# con-left-top.net
KiCad netlist of a schematic drawn in Altium Designer
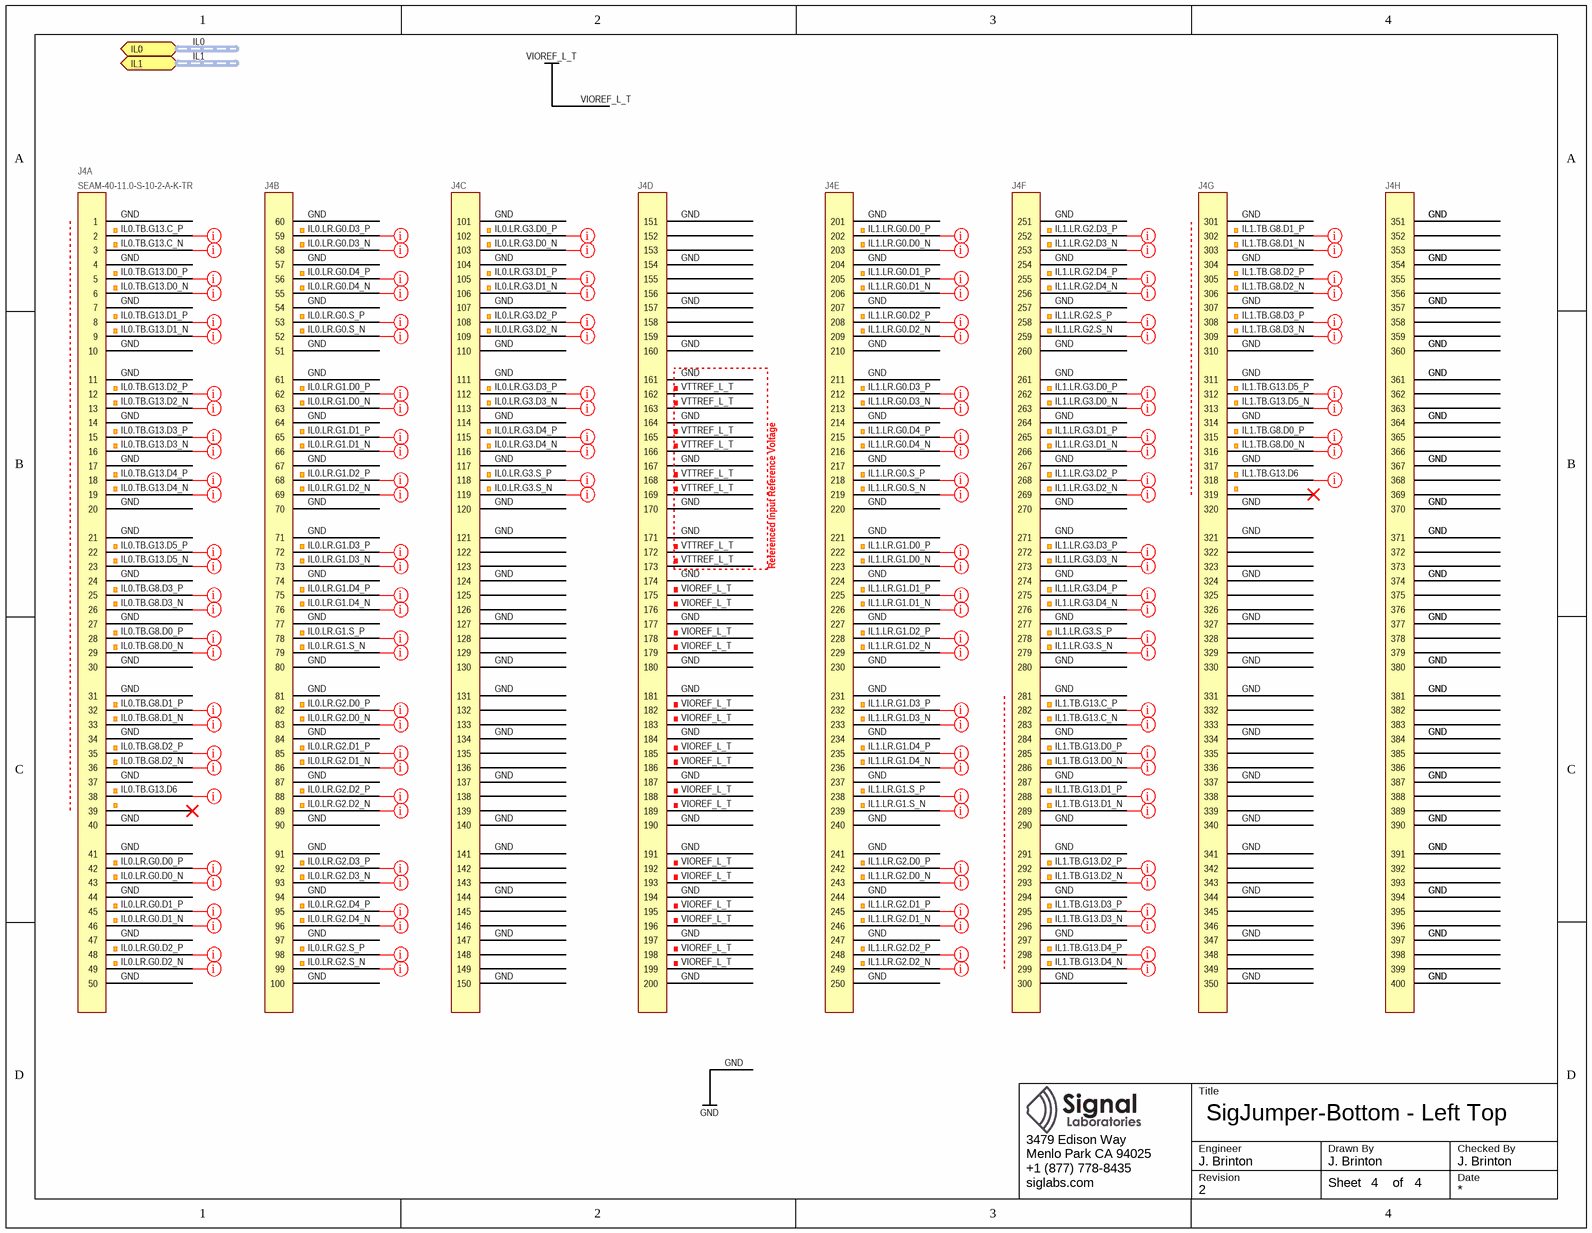
[diagram p0: con-left-top.SchDoc]

(export (version "E")
  (design (tool "Eeschema 10.0.6"))
  (components
    (comp (ref "J4")
      (value "SEAM-40-11.0-S-10-2-A-K-TR")
      (footprint "samtec:SEAM-40-11.0-S-10-2-A-K-TR")
      (description "Terminal Array Assembly, Surface Mount, 0.050\" Pitch, 400 Pins")
      (fields (field (name "MANUFACTURER") "Samtec"))
      (libsource (lib "samtec") (part "SEAM-40-11.0-S-10-2-A-K-TR"))
    )
  )
  (nets
    (net (code "3") (name "/IL0.LR.G0.D0_N") (class "Default")
      (node (ref "J4") (pin "43") (pinfunction "43_43") (pintype "passive"))
    )
    (net (code "4") (name "/IL0.LR.G0.D0_P") (class "Default")
      (node (ref "J4") (pin "42") (pinfunction "42_42") (pintype "passive"))
    )
    (net (code "5") (name "/IL0.LR.G0.D1_N") (class "Default")
      (node (ref "J4") (pin "46") (pinfunction "46_46") (pintype "passive"))
    )
    (net (code "6") (name "/IL0.LR.G0.D1_P") (class "Default")
      (node (ref "J4") (pin "45") (pinfunction "45_45") (pintype "passive"))
    )
    (net (code "7") (name "/IL0.LR.G0.D2_N") (class "Default")
      (node (ref "J4") (pin "49") (pinfunction "49_49") (pintype "passive"))
    )
    (net (code "8") (name "/IL0.LR.G0.D2_P") (class "Default")
      (node (ref "J4") (pin "48") (pinfunction "48_48") (pintype "passive"))
    )
    (net (code "9") (name "/IL0.LR.G0.D3_N") (class "Default")
      (node (ref "J4") (pin "58") (pinfunction "58_58") (pintype "passive"))
    )
    (net (code "10") (name "/IL0.LR.G0.D3_P") (class "Default")
      (node (ref "J4") (pin "59") (pinfunction "59_59") (pintype "passive"))
    )
    (net (code "11") (name "/IL0.LR.G0.D4_N") (class "Default")
      (node (ref "J4") (pin "55") (pinfunction "55_55") (pintype "passive"))
    )
    (net (code "12") (name "/IL0.LR.G0.D4_P") (class "Default")
      (node (ref "J4") (pin "56") (pinfunction "56_56") (pintype "passive"))
    )
    (net (code "13") (name "/IL0.LR.G0.S_N") (class "Default")
      (node (ref "J4") (pin "52") (pinfunction "52_52") (pintype "passive"))
    )
    (net (code "14") (name "/IL0.LR.G0.S_P") (class "Default")
      (node (ref "J4") (pin "53") (pinfunction "53_53") (pintype "passive"))
    )
    (net (code "15") (name "/IL0.LR.G1.D0_N") (class "Default")
      (node (ref "J4") (pin "63") (pinfunction "63_63") (pintype "passive"))
    )
    (net (code "16") (name "/IL0.LR.G1.D0_P") (class "Default")
      (node (ref "J4") (pin "62") (pinfunction "62_62") (pintype "passive"))
    )
    (net (code "17") (name "/IL0.LR.G1.D1_N") (class "Default")
      (node (ref "J4") (pin "66") (pinfunction "66_66") (pintype "passive"))
    )
    (net (code "18") (name "/IL0.LR.G1.D1_P") (class "Default")
      (node (ref "J4") (pin "65") (pinfunction "65_65") (pintype "passive"))
    )
    (net (code "19") (name "/IL0.LR.G1.D2_N") (class "Default")
      (node (ref "J4") (pin "69") (pinfunction "69_69") (pintype "passive"))
    )
    (net (code "20") (name "/IL0.LR.G1.D2_P") (class "Default")
      (node (ref "J4") (pin "68") (pinfunction "68_68") (pintype "passive"))
    )
    (net (code "21") (name "/IL0.LR.G1.D3_N") (class "Default")
      (node (ref "J4") (pin "73") (pinfunction "73_73") (pintype "passive"))
    )
    (net (code "22") (name "/IL0.LR.G1.D3_P") (class "Default")
      (node (ref "J4") (pin "72") (pinfunction "72_72") (pintype "passive"))
    )
    (net (code "23") (name "/IL0.LR.G1.D4_N") (class "Default")
      (node (ref "J4") (pin "76") (pinfunction "76_76") (pintype "passive"))
    )
    (net (code "24") (name "/IL0.LR.G1.D4_P") (class "Default")
      (node (ref "J4") (pin "75") (pinfunction "75_75") (pintype "passive"))
    )
    (net (code "25") (name "/IL0.LR.G1.S_N") (class "Default")
      (node (ref "J4") (pin "79") (pinfunction "79_79") (pintype "passive"))
    )
    (net (code "26") (name "/IL0.LR.G1.S_P") (class "Default")
      (node (ref "J4") (pin "78") (pinfunction "78_78") (pintype "passive"))
    )
    (net (code "27") (name "/IL0.LR.G2.D0_N") (class "Default")
      (node (ref "J4") (pin "83") (pinfunction "83_83") (pintype "passive"))
    )
    (net (code "28") (name "/IL0.LR.G2.D0_P") (class "Default")
      (node (ref "J4") (pin "82") (pinfunction "82_82") (pintype "passive"))
    )
    (net (code "29") (name "/IL0.LR.G2.D1_N") (class "Default")
      (node (ref "J4") (pin "86") (pinfunction "86_86") (pintype "passive"))
    )
    (net (code "30") (name "/IL0.LR.G2.D1_P") (class "Default")
      (node (ref "J4") (pin "85") (pinfunction "85_85") (pintype "passive"))
    )
    (net (code "31") (name "/IL0.LR.G2.D2_N") (class "Default")
      (node (ref "J4") (pin "89") (pinfunction "89_89") (pintype "passive"))
    )
    (net (code "32") (name "/IL0.LR.G2.D2_P") (class "Default")
      (node (ref "J4") (pin "88") (pinfunction "88_88") (pintype "passive"))
    )
    (net (code "33") (name "/IL0.LR.G2.D3_N") (class "Default")
      (node (ref "J4") (pin "93") (pinfunction "93_93") (pintype "passive"))
    )
    (net (code "34") (name "/IL0.LR.G2.D3_P") (class "Default")
      (node (ref "J4") (pin "92") (pinfunction "92_92") (pintype "passive"))
    )
    (net (code "35") (name "/IL0.LR.G2.D4_N") (class "Default")
      (node (ref "J4") (pin "96") (pinfunction "96_96") (pintype "passive"))
    )
    (net (code "36") (name "/IL0.LR.G2.D4_P") (class "Default")
      (node (ref "J4") (pin "95") (pinfunction "95_95") (pintype "passive"))
    )
    (net (code "37") (name "/IL0.LR.G2.S_N") (class "Default")
      (node (ref "J4") (pin "99") (pinfunction "99_99") (pintype "passive"))
    )
    (net (code "38") (name "/IL0.LR.G2.S_P") (class "Default")
      (node (ref "J4") (pin "98") (pinfunction "98_98") (pintype "passive"))
    )
    (net (code "39") (name "/IL0.LR.G3.D0_N") (class "Default")
      (node (ref "J4") (pin "103") (pinfunction "103_103") (pintype "passive"))
    )
    (net (code "40") (name "/IL0.LR.G3.D0_P") (class "Default")
      (node (ref "J4") (pin "102") (pinfunction "102_102") (pintype "passive"))
    )
    (net (code "41") (name "/IL0.LR.G3.D1_N") (class "Default")
      (node (ref "J4") (pin "106") (pinfunction "106_106") (pintype "passive"))
    )
    (net (code "42") (name "/IL0.LR.G3.D1_P") (class "Default")
      (node (ref "J4") (pin "105") (pinfunction "105_105") (pintype "passive"))
    )
    (net (code "43") (name "/IL0.LR.G3.D2_N") (class "Default")
      (node (ref "J4") (pin "109") (pinfunction "109_109") (pintype "passive"))
    )
    (net (code "44") (name "/IL0.LR.G3.D2_P") (class "Default")
      (node (ref "J4") (pin "108") (pinfunction "108_108") (pintype "passive"))
    )
    (net (code "45") (name "/IL0.LR.G3.D3_N") (class "Default")
      (node (ref "J4") (pin "113") (pinfunction "113_113") (pintype "passive"))
    )
    (net (code "46") (name "/IL0.LR.G3.D3_P") (class "Default")
      (node (ref "J4") (pin "112") (pinfunction "112_112") (pintype "passive"))
    )
    (net (code "47") (name "/IL0.LR.G3.D4_N") (class "Default")
      (node (ref "J4") (pin "116") (pinfunction "116_116") (pintype "passive"))
    )
    (net (code "48") (name "/IL0.LR.G3.D4_P") (class "Default")
      (node (ref "J4") (pin "115") (pinfunction "115_115") (pintype "passive"))
    )
    (net (code "49") (name "/IL0.LR.G3.S_N") (class "Default")
      (node (ref "J4") (pin "119") (pinfunction "119_119") (pintype "passive"))
    )
    (net (code "50") (name "/IL0.LR.G3.S_P") (class "Default")
      (node (ref "J4") (pin "118") (pinfunction "118_118") (pintype "passive"))
    )
    (net (code "51") (name "/IL0.TB.G8.D0_N") (class "Default")
      (node (ref "J4") (pin "29") (pinfunction "29_29") (pintype "passive"))
    )
    (net (code "52") (name "/IL0.TB.G8.D0_P") (class "Default")
      (node (ref "J4") (pin "28") (pinfunction "28_28") (pintype "passive"))
    )
    (net (code "53") (name "/IL0.TB.G8.D1_N") (class "Default")
      (node (ref "J4") (pin "33") (pinfunction "33_33") (pintype "passive"))
    )
    (net (code "54") (name "/IL0.TB.G8.D1_P") (class "Default")
      (node (ref "J4") (pin "32") (pinfunction "32_32") (pintype "passive"))
    )
    (net (code "55") (name "/IL0.TB.G8.D2_N") (class "Default")
      (node (ref "J4") (pin "36") (pinfunction "36_36") (pintype "passive"))
    )
    (net (code "56") (name "/IL0.TB.G8.D2_P") (class "Default")
      (node (ref "J4") (pin "35") (pinfunction "35_35") (pintype "passive"))
    )
    (net (code "57") (name "/IL0.TB.G8.D3_N") (class "Default")
      (node (ref "J4") (pin "26") (pinfunction "26_26") (pintype "passive"))
    )
    (net (code "58") (name "/IL0.TB.G8.D3_P") (class "Default")
      (node (ref "J4") (pin "25") (pinfunction "25_25") (pintype "passive"))
    )
    (net (code "59") (name "/IL0.TB.G13.C_N") (class "Default")
      (node (ref "J4") (pin "3") (pinfunction "3_3") (pintype "passive"))
    )
    (net (code "60") (name "/IL0.TB.G13.C_P") (class "Default")
      (node (ref "J4") (pin "2") (pinfunction "2_2") (pintype "passive"))
    )
    (net (code "61") (name "/IL0.TB.G13.D0_N") (class "Default")
      (node (ref "J4") (pin "6") (pinfunction "6_6") (pintype "passive"))
    )
    (net (code "62") (name "/IL0.TB.G13.D0_P") (class "Default")
      (node (ref "J4") (pin "5") (pinfunction "5_5") (pintype "passive"))
    )
    (net (code "63") (name "/IL0.TB.G13.D1_N") (class "Default")
      (node (ref "J4") (pin "9") (pinfunction "9_9") (pintype "passive"))
    )
    (net (code "64") (name "/IL0.TB.G13.D1_P") (class "Default")
      (node (ref "J4") (pin "8") (pinfunction "8_8") (pintype "passive"))
    )
    (net (code "65") (name "/IL0.TB.G13.D2_N") (class "Default")
      (node (ref "J4") (pin "13") (pinfunction "13_13") (pintype "passive"))
    )
    (net (code "66") (name "/IL0.TB.G13.D2_P") (class "Default")
      (node (ref "J4") (pin "12") (pinfunction "12_12") (pintype "passive"))
    )
    (net (code "67") (name "/IL0.TB.G13.D3_N") (class "Default")
      (node (ref "J4") (pin "16") (pinfunction "16_16") (pintype "passive"))
    )
    (net (code "68") (name "/IL0.TB.G13.D3_P") (class "Default")
      (node (ref "J4") (pin "15") (pinfunction "15_15") (pintype "passive"))
    )
    (net (code "69") (name "/IL0.TB.G13.D4_N") (class "Default")
      (node (ref "J4") (pin "19") (pinfunction "19_19") (pintype "passive"))
    )
    (net (code "70") (name "/IL0.TB.G13.D4_P") (class "Default")
      (node (ref "J4") (pin "18") (pinfunction "18_18") (pintype "passive"))
    )
    (net (code "71") (name "/IL0.TB.G13.D5_N") (class "Default")
      (node (ref "J4") (pin "23") (pinfunction "23_23") (pintype "passive"))
    )
    (net (code "72") (name "/IL0.TB.G13.D5_P") (class "Default")
      (node (ref "J4") (pin "22") (pinfunction "22_22") (pintype "passive"))
    )
    (net (code "73") (name "/IL0.TB.G13.D6") (class "Default")
      (node (ref "J4") (pin "38") (pinfunction "38_38") (pintype "passive"))
    )
    (net (code "74") (name "/IL1.LR.G0.D0_N") (class "Default")
      (node (ref "J4") (pin "203") (pinfunction "203_203") (pintype "passive"))
    )
    (net (code "75") (name "/IL1.LR.G0.D0_P") (class "Default")
      (node (ref "J4") (pin "202") (pinfunction "202_202") (pintype "passive"))
    )
    (net (code "76") (name "/IL1.LR.G0.D1_N") (class "Default")
      (node (ref "J4") (pin "206") (pinfunction "206_206") (pintype "passive"))
    )
    (net (code "77") (name "/IL1.LR.G0.D1_P") (class "Default")
      (node (ref "J4") (pin "205") (pinfunction "205_205") (pintype "passive"))
    )
    (net (code "78") (name "/IL1.LR.G0.D2_N") (class "Default")
      (node (ref "J4") (pin "209") (pinfunction "209_209") (pintype "passive"))
    )
    (net (code "79") (name "/IL1.LR.G0.D2_P") (class "Default")
      (node (ref "J4") (pin "208") (pinfunction "208_208") (pintype "passive"))
    )
    (net (code "80") (name "/IL1.LR.G0.D3_N") (class "Default")
      (node (ref "J4") (pin "213") (pinfunction "213_213") (pintype "passive"))
    )
    (net (code "81") (name "/IL1.LR.G0.D3_P") (class "Default")
      (node (ref "J4") (pin "212") (pinfunction "212_212") (pintype "passive"))
    )
    (net (code "82") (name "/IL1.LR.G0.D4_N") (class "Default")
      (node (ref "J4") (pin "216") (pinfunction "216_216") (pintype "passive"))
    )
    (net (code "83") (name "/IL1.LR.G0.D4_P") (class "Default")
      (node (ref "J4") (pin "215") (pinfunction "215_215") (pintype "passive"))
    )
    (net (code "84") (name "/IL1.LR.G0.S_N") (class "Default")
      (node (ref "J4") (pin "219") (pinfunction "219_219") (pintype "passive"))
    )
    (net (code "85") (name "/IL1.LR.G0.S_P") (class "Default")
      (node (ref "J4") (pin "218") (pinfunction "218_218") (pintype "passive"))
    )
    (net (code "86") (name "/IL1.LR.G1.D0_N") (class "Default")
      (node (ref "J4") (pin "223") (pinfunction "223_223") (pintype "passive"))
    )
    (net (code "87") (name "/IL1.LR.G1.D0_P") (class "Default")
      (node (ref "J4") (pin "222") (pinfunction "222_222") (pintype "passive"))
    )
    (net (code "88") (name "/IL1.LR.G1.D1_N") (class "Default")
      (node (ref "J4") (pin "226") (pinfunction "226_226") (pintype "passive"))
    )
    (net (code "89") (name "/IL1.LR.G1.D1_P") (class "Default")
      (node (ref "J4") (pin "225") (pinfunction "225_225") (pintype "passive"))
    )
    (net (code "90") (name "/IL1.LR.G1.D2_N") (class "Default")
      (node (ref "J4") (pin "229") (pinfunction "229_229") (pintype "passive"))
    )
    (net (code "91") (name "/IL1.LR.G1.D2_P") (class "Default")
      (node (ref "J4") (pin "228") (pinfunction "228_228") (pintype "passive"))
    )
    (net (code "92") (name "/IL1.LR.G1.D3_N") (class "Default")
      (node (ref "J4") (pin "233") (pinfunction "233_233") (pintype "passive"))
    )
    (net (code "93") (name "/IL1.LR.G1.D3_P") (class "Default")
      (node (ref "J4") (pin "232") (pinfunction "232_232") (pintype "passive"))
    )
    (net (code "94") (name "/IL1.LR.G1.D4_N") (class "Default")
      (node (ref "J4") (pin "236") (pinfunction "236_236") (pintype "passive"))
    )
    (net (code "95") (name "/IL1.LR.G1.D4_P") (class "Default")
      (node (ref "J4") (pin "235") (pinfunction "235_235") (pintype "passive"))
    )
    (net (code "96") (name "/IL1.LR.G1.S_N") (class "Default")
      (node (ref "J4") (pin "239") (pinfunction "239_239") (pintype "passive"))
    )
    (net (code "97") (name "/IL1.LR.G1.S_P") (class "Default")
      (node (ref "J4") (pin "238") (pinfunction "238_238") (pintype "passive"))
    )
    (net (code "98") (name "/IL1.LR.G2.D0_N") (class "Default")
      (node (ref "J4") (pin "243") (pinfunction "243_243") (pintype "passive"))
    )
    (net (code "99") (name "/IL1.LR.G2.D0_P") (class "Default")
      (node (ref "J4") (pin "242") (pinfunction "242_242") (pintype "passive"))
    )
    (net (code "100") (name "/IL1.LR.G2.D1_N") (class "Default")
      (node (ref "J4") (pin "246") (pinfunction "246_246") (pintype "passive"))
    )
    (net (code "101") (name "/IL1.LR.G2.D1_P") (class "Default")
      (node (ref "J4") (pin "245") (pinfunction "245_245") (pintype "passive"))
    )
    (net (code "102") (name "/IL1.LR.G2.D2_N") (class "Default")
      (node (ref "J4") (pin "249") (pinfunction "249_249") (pintype "passive"))
    )
    (net (code "103") (name "/IL1.LR.G2.D2_P") (class "Default")
      (node (ref "J4") (pin "248") (pinfunction "248_248") (pintype "passive"))
    )
    (net (code "104") (name "/IL1.LR.G2.D3_N") (class "Default")
      (node (ref "J4") (pin "253") (pinfunction "253_253") (pintype "passive"))
    )
    (net (code "105") (name "/IL1.LR.G2.D3_P") (class "Default")
      (node (ref "J4") (pin "252") (pinfunction "252_252") (pintype "passive"))
    )
    (net (code "106") (name "/IL1.LR.G2.D4_N") (class "Default")
      (node (ref "J4") (pin "256") (pinfunction "256_256") (pintype "passive"))
    )
    (net (code "107") (name "/IL1.LR.G2.D4_P") (class "Default")
      (node (ref "J4") (pin "255") (pinfunction "255_255") (pintype "passive"))
    )
    (net (code "108") (name "/IL1.LR.G2.S_N") (class "Default")
      (node (ref "J4") (pin "259") (pinfunction "259_259") (pintype "passive"))
    )
    (net (code "109") (name "/IL1.LR.G2.S_P") (class "Default")
      (node (ref "J4") (pin "258") (pinfunction "258_258") (pintype "passive"))
    )
    (net (code "110") (name "/IL1.LR.G3.D0_N") (class "Default")
      (node (ref "J4") (pin "263") (pinfunction "263_263") (pintype "passive"))
    )
    (net (code "111") (name "/IL1.LR.G3.D0_P") (class "Default")
      (node (ref "J4") (pin "262") (pinfunction "262_262") (pintype "passive"))
    )
    (net (code "112") (name "/IL1.LR.G3.D1_N") (class "Default")
      (node (ref "J4") (pin "266") (pinfunction "266_266") (pintype "passive"))
    )
    (net (code "113") (name "/IL1.LR.G3.D1_P") (class "Default")
      (node (ref "J4") (pin "265") (pinfunction "265_265") (pintype "passive"))
    )
    (net (code "114") (name "/IL1.LR.G3.D2_N") (class "Default")
      (node (ref "J4") (pin "269") (pinfunction "269_269") (pintype "passive"))
    )
    (net (code "115") (name "/IL1.LR.G3.D2_P") (class "Default")
      (node (ref "J4") (pin "268") (pinfunction "268_268") (pintype "passive"))
    )
    (net (code "116") (name "/IL1.LR.G3.D3_N") (class "Default")
      (node (ref "J4") (pin "273") (pinfunction "273_273") (pintype "passive"))
    )
    (net (code "117") (name "/IL1.LR.G3.D3_P") (class "Default")
      (node (ref "J4") (pin "272") (pinfunction "272_272") (pintype "passive"))
    )
    (net (code "118") (name "/IL1.LR.G3.D4_N") (class "Default")
      (node (ref "J4") (pin "276") (pinfunction "276_276") (pintype "passive"))
    )
    (net (code "119") (name "/IL1.LR.G3.D4_P") (class "Default")
      (node (ref "J4") (pin "275") (pinfunction "275_275") (pintype "passive"))
    )
    (net (code "120") (name "/IL1.LR.G3.S_N") (class "Default")
      (node (ref "J4") (pin "279") (pinfunction "279_279") (pintype "passive"))
    )
    (net (code "121") (name "/IL1.LR.G3.S_P") (class "Default")
      (node (ref "J4") (pin "278") (pinfunction "278_278") (pintype "passive"))
    )
    (net (code "122") (name "/IL1.TB.G8.D0_N") (class "Default")
      (node (ref "J4") (pin "316") (pinfunction "316_316") (pintype "passive"))
    )
    (net (code "123") (name "/IL1.TB.G8.D0_P") (class "Default")
      (node (ref "J4") (pin "315") (pinfunction "315_315") (pintype "passive"))
    )
    (net (code "124") (name "/IL1.TB.G8.D1_N") (class "Default")
      (node (ref "J4") (pin "303") (pinfunction "303_303") (pintype "passive"))
    )
    (net (code "125") (name "/IL1.TB.G8.D1_P") (class "Default")
      (node (ref "J4") (pin "302") (pinfunction "302_302") (pintype "passive"))
    )
    (net (code "126") (name "/IL1.TB.G8.D2_N") (class "Default")
      (node (ref "J4") (pin "306") (pinfunction "306_306") (pintype "passive"))
    )
    (net (code "127") (name "/IL1.TB.G8.D2_P") (class "Default")
      (node (ref "J4") (pin "305") (pinfunction "305_305") (pintype "passive"))
    )
    (net (code "128") (name "/IL1.TB.G8.D3_N") (class "Default")
      (node (ref "J4") (pin "309") (pinfunction "309_309") (pintype "passive"))
    )
    (net (code "129") (name "/IL1.TB.G8.D3_P") (class "Default")
      (node (ref "J4") (pin "308") (pinfunction "308_308") (pintype "passive"))
    )
    (net (code "130") (name "/IL1.TB.G13.C_N") (class "Default")
      (node (ref "J4") (pin "283") (pinfunction "283_283") (pintype "passive"))
    )
    (net (code "131") (name "/IL1.TB.G13.C_P") (class "Default")
      (node (ref "J4") (pin "282") (pinfunction "282_282") (pintype "passive"))
    )
    (net (code "132") (name "/IL1.TB.G13.D0_N") (class "Default")
      (node (ref "J4") (pin "286") (pinfunction "286_286") (pintype "passive"))
    )
    (net (code "133") (name "/IL1.TB.G13.D0_P") (class "Default")
      (node (ref "J4") (pin "285") (pinfunction "285_285") (pintype "passive"))
    )
    (net (code "134") (name "/IL1.TB.G13.D1_N") (class "Default")
      (node (ref "J4") (pin "289") (pinfunction "289_289") (pintype "passive"))
    )
    (net (code "135") (name "/IL1.TB.G13.D1_P") (class "Default")
      (node (ref "J4") (pin "288") (pinfunction "288_288") (pintype "passive"))
    )
    (net (code "136") (name "/IL1.TB.G13.D2_N") (class "Default")
      (node (ref "J4") (pin "293") (pinfunction "293_293") (pintype "passive"))
    )
    (net (code "137") (name "/IL1.TB.G13.D2_P") (class "Default")
      (node (ref "J4") (pin "292") (pinfunction "292_292") (pintype "passive"))
    )
    (net (code "138") (name "/IL1.TB.G13.D3_N") (class "Default")
      (node (ref "J4") (pin "296") (pinfunction "296_296") (pintype "passive"))
    )
    (net (code "139") (name "/IL1.TB.G13.D3_P") (class "Default")
      (node (ref "J4") (pin "295") (pinfunction "295_295") (pintype "passive"))
    )
    (net (code "140") (name "/IL1.TB.G13.D4_N") (class "Default")
      (node (ref "J4") (pin "299") (pinfunction "299_299") (pintype "passive"))
    )
    (net (code "141") (name "/IL1.TB.G13.D4_P") (class "Default")
      (node (ref "J4") (pin "298") (pinfunction "298_298") (pintype "passive"))
    )
    (net (code "142") (name "/IL1.TB.G13.D5_N") (class "Default")
      (node (ref "J4") (pin "313") (pinfunction "313_313") (pintype "passive"))
    )
    (net (code "143") (name "/IL1.TB.G13.D5_P") (class "Default")
      (node (ref "J4") (pin "312") (pinfunction "312_312") (pintype "passive"))
    )
    (net (code "144") (name "/IL1.TB.G13.D6") (class "Default")
      (node (ref "J4") (pin "318") (pinfunction "318_318") (pintype "passive"))
    )
    (net (code "145") (name "/VTTREF_L_T") (class "Default")
      (node (ref "J4") (pin "162") (pinfunction "162_162") (pintype "passive"))
      (node (ref "J4") (pin "163") (pinfunction "163_163") (pintype "passive"))
      (node (ref "J4") (pin "165") (pinfunction "165_165") (pintype "passive"))
      (node (ref "J4") (pin "166") (pinfunction "166_166") (pintype "passive"))
      (node (ref "J4") (pin "168") (pinfunction "168_168") (pintype "passive"))
      (node (ref "J4") (pin "169") (pinfunction "169_169") (pintype "passive"))
      (node (ref "J4") (pin "172") (pinfunction "172_172") (pintype "passive"))
      (node (ref "J4") (pin "173") (pinfunction "173_173") (pintype "passive"))
    )
    (net (code "148") (name "GND") (class "Default")
      (node (ref "J4") (pin "1") (pinfunction "1_1") (pintype "passive"))
      (node (ref "J4") (pin "10") (pinfunction "10_10") (pintype "passive"))
      (node (ref "J4") (pin "100") (pinfunction "100_100") (pintype "passive"))
      (node (ref "J4") (pin "101") (pinfunction "101_101") (pintype "passive"))
      (node (ref "J4") (pin "104") (pinfunction "104_104") (pintype "passive"))
      (node (ref "J4") (pin "107") (pinfunction "107_107") (pintype "passive"))
      (node (ref "J4") (pin "11") (pinfunction "11_11") (pintype "passive"))
      (node (ref "J4") (pin "110") (pinfunction "110_110") (pintype "passive"))
      (node (ref "J4") (pin "111") (pinfunction "111_111") (pintype "passive"))
      (node (ref "J4") (pin "114") (pinfunction "114_114") (pintype "passive"))
      (node (ref "J4") (pin "117") (pinfunction "117_117") (pintype "passive"))
      (node (ref "J4") (pin "120") (pinfunction "120_120") (pintype "passive"))
      (node (ref "J4") (pin "121") (pinfunction "121_121") (pintype "passive"))
      (node (ref "J4") (pin "124") (pinfunction "124_124") (pintype "passive"))
      (node (ref "J4") (pin "127") (pinfunction "127_127") (pintype "passive"))
      (node (ref "J4") (pin "130") (pinfunction "130_130") (pintype "passive"))
      (node (ref "J4") (pin "131") (pinfunction "131_131") (pintype "passive"))
      (node (ref "J4") (pin "134") (pinfunction "134_134") (pintype "passive"))
      (node (ref "J4") (pin "137") (pinfunction "137_137") (pintype "passive"))
      (node (ref "J4") (pin "14") (pinfunction "14_14") (pintype "passive"))
      (node (ref "J4") (pin "140") (pinfunction "140_140") (pintype "passive"))
      (node (ref "J4") (pin "141") (pinfunction "141_141") (pintype "passive"))
      (node (ref "J4") (pin "144") (pinfunction "144_144") (pintype "passive"))
      (node (ref "J4") (pin "147") (pinfunction "147_147") (pintype "passive"))
      (node (ref "J4") (pin "150") (pinfunction "150_150") (pintype "passive"))
      (node (ref "J4") (pin "151") (pinfunction "151_151") (pintype "passive"))
      (node (ref "J4") (pin "154") (pinfunction "154_154") (pintype "passive"))
      (node (ref "J4") (pin "157") (pinfunction "157_157") (pintype "passive"))
      (node (ref "J4") (pin "160") (pinfunction "160_160") (pintype "passive"))
      (node (ref "J4") (pin "161") (pinfunction "161_161") (pintype "passive"))
      (node (ref "J4") (pin "164") (pinfunction "164_164") (pintype "passive"))
      (node (ref "J4") (pin "167") (pinfunction "167_167") (pintype "passive"))
      (node (ref "J4") (pin "17") (pinfunction "17_17") (pintype "passive"))
      (node (ref "J4") (pin "170") (pinfunction "170_170") (pintype "passive"))
      (node (ref "J4") (pin "171") (pinfunction "171_171") (pintype "passive"))
      (node (ref "J4") (pin "174") (pinfunction "174_174") (pintype "passive"))
      (node (ref "J4") (pin "177") (pinfunction "177_177") (pintype "passive"))
      (node (ref "J4") (pin "180") (pinfunction "180_180") (pintype "passive"))
      (node (ref "J4") (pin "181") (pinfunction "181_181") (pintype "passive"))
      (node (ref "J4") (pin "184") (pinfunction "184_184") (pintype "passive"))
      (node (ref "J4") (pin "187") (pinfunction "187_187") (pintype "passive"))
      (node (ref "J4") (pin "190") (pinfunction "190_190") (pintype "passive"))
      (node (ref "J4") (pin "191") (pinfunction "191_191") (pintype "passive"))
      (node (ref "J4") (pin "194") (pinfunction "194_194") (pintype "passive"))
      (node (ref "J4") (pin "197") (pinfunction "197_197") (pintype "passive"))
      (node (ref "J4") (pin "20") (pinfunction "20_20") (pintype "passive"))
      (node (ref "J4") (pin "200") (pinfunction "200_200") (pintype "passive"))
      (node (ref "J4") (pin "201") (pinfunction "201_201") (pintype "passive"))
      (node (ref "J4") (pin "204") (pinfunction "204_204") (pintype "passive"))
      (node (ref "J4") (pin "207") (pinfunction "207_207") (pintype "passive"))
      (node (ref "J4") (pin "21") (pinfunction "21_21") (pintype "passive"))
      (node (ref "J4") (pin "210") (pinfunction "210_210") (pintype "passive"))
      (node (ref "J4") (pin "211") (pinfunction "211_211") (pintype "passive"))
      (node (ref "J4") (pin "214") (pinfunction "214_214") (pintype "passive"))
      (node (ref "J4") (pin "217") (pinfunction "217_217") (pintype "passive"))
      (node (ref "J4") (pin "220") (pinfunction "220_220") (pintype "passive"))
      (node (ref "J4") (pin "221") (pinfunction "221_221") (pintype "passive"))
      (node (ref "J4") (pin "224") (pinfunction "224_224") (pintype "passive"))
      (node (ref "J4") (pin "227") (pinfunction "227_227") (pintype "passive"))
      (node (ref "J4") (pin "230") (pinfunction "230_230") (pintype "passive"))
      (node (ref "J4") (pin "231") (pinfunction "231_231") (pintype "passive"))
      (node (ref "J4") (pin "234") (pinfunction "234_234") (pintype "passive"))
      (node (ref "J4") (pin "237") (pinfunction "237_237") (pintype "passive"))
      (node (ref "J4") (pin "24") (pinfunction "24_24") (pintype "passive"))
      (node (ref "J4") (pin "240") (pinfunction "240_240") (pintype "passive"))
      (node (ref "J4") (pin "241") (pinfunction "241_241") (pintype "passive"))
      (node (ref "J4") (pin "244") (pinfunction "244_244") (pintype "passive"))
      (node (ref "J4") (pin "247") (pinfunction "247_247") (pintype "passive"))
      (node (ref "J4") (pin "250") (pinfunction "250_250") (pintype "passive"))
      (node (ref "J4") (pin "251") (pinfunction "251_251") (pintype "passive"))
      (node (ref "J4") (pin "254") (pinfunction "254_254") (pintype "passive"))
      (node (ref "J4") (pin "257") (pinfunction "257_257") (pintype "passive"))
      (node (ref "J4") (pin "260") (pinfunction "260_260") (pintype "passive"))
      (node (ref "J4") (pin "261") (pinfunction "261_261") (pintype "passive"))
      (node (ref "J4") (pin "264") (pinfunction "264_264") (pintype "passive"))
      (node (ref "J4") (pin "267") (pinfunction "267_267") (pintype "passive"))
      (node (ref "J4") (pin "27") (pinfunction "27_27") (pintype "passive"))
      (node (ref "J4") (pin "270") (pinfunction "270_270") (pintype "passive"))
      (node (ref "J4") (pin "271") (pinfunction "271_271") (pintype "passive"))
      (node (ref "J4") (pin "274") (pinfunction "274_274") (pintype "passive"))
      (node (ref "J4") (pin "277") (pinfunction "277_277") (pintype "passive"))
      (node (ref "J4") (pin "280") (pinfunction "280_280") (pintype "passive"))
      (node (ref "J4") (pin "281") (pinfunction "281_281") (pintype "passive"))
      (node (ref "J4") (pin "284") (pinfunction "284_284") (pintype "passive"))
      (node (ref "J4") (pin "287") (pinfunction "287_287") (pintype "passive"))
      (node (ref "J4") (pin "290") (pinfunction "290_290") (pintype "passive"))
      (node (ref "J4") (pin "291") (pinfunction "291_291") (pintype "passive"))
      (node (ref "J4") (pin "294") (pinfunction "294_294") (pintype "passive"))
      (node (ref "J4") (pin "297") (pinfunction "297_297") (pintype "passive"))
      (node (ref "J4") (pin "30") (pinfunction "30_30") (pintype "passive"))
      (node (ref "J4") (pin "300") (pinfunction "300_300") (pintype "passive"))
      (node (ref "J4") (pin "301") (pinfunction "301_301") (pintype "passive"))
      (node (ref "J4") (pin "304") (pinfunction "304_304") (pintype "passive"))
      (node (ref "J4") (pin "307") (pinfunction "307_307") (pintype "passive"))
      (node (ref "J4") (pin "31") (pinfunction "31_31") (pintype "passive"))
      (node (ref "J4") (pin "310") (pinfunction "310_310") (pintype "passive"))
      (node (ref "J4") (pin "311") (pinfunction "311_311") (pintype "passive"))
      (node (ref "J4") (pin "314") (pinfunction "314_314") (pintype "passive"))
      (node (ref "J4") (pin "317") (pinfunction "317_317") (pintype "passive"))
      (node (ref "J4") (pin "320") (pinfunction "320_320") (pintype "passive"))
      (node (ref "J4") (pin "321") (pinfunction "321_321") (pintype "passive"))
      (node (ref "J4") (pin "324") (pinfunction "324_324") (pintype "passive"))
      (node (ref "J4") (pin "327") (pinfunction "327_327") (pintype "passive"))
      (node (ref "J4") (pin "330") (pinfunction "330_330") (pintype "passive"))
      (node (ref "J4") (pin "331") (pinfunction "331_331") (pintype "passive"))
      (node (ref "J4") (pin "334") (pinfunction "334_334") (pintype "passive"))
      (node (ref "J4") (pin "337") (pinfunction "337_337") (pintype "passive"))
      (node (ref "J4") (pin "34") (pinfunction "34_34") (pintype "passive"))
      (node (ref "J4") (pin "340") (pinfunction "340_340") (pintype "passive"))
      (node (ref "J4") (pin "341") (pinfunction "341_341") (pintype "passive"))
      (node (ref "J4") (pin "344") (pinfunction "344_344") (pintype "passive"))
      (node (ref "J4") (pin "347") (pinfunction "347_347") (pintype "passive"))
      (node (ref "J4") (pin "350") (pinfunction "350_350") (pintype "passive"))
      (node (ref "J4") (pin "351") (pinfunction "351_351") (pintype "passive"))
      (node (ref "J4") (pin "354") (pinfunction "354_354") (pintype "passive"))
      (node (ref "J4") (pin "357") (pinfunction "357_357") (pintype "passive"))
      (node (ref "J4") (pin "360") (pinfunction "360_360") (pintype "passive"))
      (node (ref "J4") (pin "361") (pinfunction "361_361") (pintype "passive"))
      (node (ref "J4") (pin "364") (pinfunction "364_364") (pintype "passive"))
      (node (ref "J4") (pin "367") (pinfunction "367_367") (pintype "passive"))
      (node (ref "J4") (pin "37") (pinfunction "37_37") (pintype "passive"))
      (node (ref "J4") (pin "370") (pinfunction "370_370") (pintype "passive"))
      (node (ref "J4") (pin "371") (pinfunction "371_371") (pintype "passive"))
      (node (ref "J4") (pin "374") (pinfunction "374_374") (pintype "passive"))
      (node (ref "J4") (pin "377") (pinfunction "377_377") (pintype "passive"))
      (node (ref "J4") (pin "380") (pinfunction "380_380") (pintype "passive"))
      (node (ref "J4") (pin "381") (pinfunction "381_381") (pintype "passive"))
      (node (ref "J4") (pin "384") (pinfunction "384_384") (pintype "passive"))
      (node (ref "J4") (pin "387") (pinfunction "387_387") (pintype "passive"))
      (node (ref "J4") (pin "390") (pinfunction "390_390") (pintype "passive"))
      (node (ref "J4") (pin "391") (pinfunction "391_391") (pintype "passive"))
      (node (ref "J4") (pin "394") (pinfunction "394_394") (pintype "passive"))
      (node (ref "J4") (pin "397") (pinfunction "397_397") (pintype "passive"))
      (node (ref "J4") (pin "4") (pinfunction "4_4") (pintype "passive"))
      (node (ref "J4") (pin "40") (pinfunction "40_40") (pintype "passive"))
      (node (ref "J4") (pin "400") (pinfunction "400_400") (pintype "passive"))
      (node (ref "J4") (pin "41") (pinfunction "41_41") (pintype "passive"))
      (node (ref "J4") (pin "44") (pinfunction "44_44") (pintype "passive"))
      (node (ref "J4") (pin "47") (pinfunction "47_47") (pintype "passive"))
      (node (ref "J4") (pin "50") (pinfunction "50_50") (pintype "passive"))
      (node (ref "J4") (pin "51") (pinfunction "51_51") (pintype "passive"))
      (node (ref "J4") (pin "54") (pinfunction "54_54") (pintype "passive"))
      (node (ref "J4") (pin "57") (pinfunction "57_57") (pintype "passive"))
      (node (ref "J4") (pin "60") (pinfunction "60_60") (pintype "passive"))
      (node (ref "J4") (pin "61") (pinfunction "61_61") (pintype "passive"))
      (node (ref "J4") (pin "64") (pinfunction "64_64") (pintype "passive"))
      (node (ref "J4") (pin "67") (pinfunction "67_67") (pintype "passive"))
      (node (ref "J4") (pin "7") (pinfunction "7_7") (pintype "passive"))
      (node (ref "J4") (pin "70") (pinfunction "70_70") (pintype "passive"))
      (node (ref "J4") (pin "71") (pinfunction "71_71") (pintype "passive"))
      (node (ref "J4") (pin "74") (pinfunction "74_74") (pintype "passive"))
      (node (ref "J4") (pin "77") (pinfunction "77_77") (pintype "passive"))
      (node (ref "J4") (pin "80") (pinfunction "80_80") (pintype "passive"))
      (node (ref "J4") (pin "81") (pinfunction "81_81") (pintype "passive"))
      (node (ref "J4") (pin "84") (pinfunction "84_84") (pintype "passive"))
      (node (ref "J4") (pin "87") (pinfunction "87_87") (pintype "passive"))
      (node (ref "J4") (pin "90") (pinfunction "90_90") (pintype "passive"))
      (node (ref "J4") (pin "91") (pinfunction "91_91") (pintype "passive"))
      (node (ref "J4") (pin "94") (pinfunction "94_94") (pintype "passive"))
      (node (ref "J4") (pin "97") (pinfunction "97_97") (pintype "passive"))
    )
    (net (code "149") (name "VIOREF_L_T") (class "Default")
      (node (ref "J4") (pin "175") (pinfunction "175_175") (pintype "passive"))
      (node (ref "J4") (pin "176") (pinfunction "176_176") (pintype "passive"))
      (node (ref "J4") (pin "178") (pinfunction "178_178") (pintype "passive"))
      (node (ref "J4") (pin "179") (pinfunction "179_179") (pintype "passive"))
      (node (ref "J4") (pin "182") (pinfunction "182_182") (pintype "passive"))
      (node (ref "J4") (pin "183") (pinfunction "183_183") (pintype "passive"))
      (node (ref "J4") (pin "185") (pinfunction "185_185") (pintype "passive"))
      (node (ref "J4") (pin "186") (pinfunction "186_186") (pintype "passive"))
      (node (ref "J4") (pin "188") (pinfunction "188_188") (pintype "passive"))
      (node (ref "J4") (pin "189") (pinfunction "189_189") (pintype "passive"))
      (node (ref "J4") (pin "192") (pinfunction "192_192") (pintype "passive"))
      (node (ref "J4") (pin "193") (pinfunction "193_193") (pintype "passive"))
      (node (ref "J4") (pin "195") (pinfunction "195_195") (pintype "passive"))
      (node (ref "J4") (pin "196") (pinfunction "196_196") (pintype "passive"))
      (node (ref "J4") (pin "198") (pinfunction "198_198") (pintype "passive"))
      (node (ref "J4") (pin "199") (pinfunction "199_199") (pintype "passive"))
    )
    (net (code "150") (name "unconnected-(J4-Pad39)") (class "Default")
      (node (ref "J4") (pin "39") (pinfunction "39_39") (pintype "passive+no_connect"))
    )
    (net (code "151") (name "unconnected-(J4-Pad122)") (class "Default")
      (node (ref "J4") (pin "122") (pinfunction "122_122") (pintype "passive"))
    )
    (net (code "152") (name "unconnected-(J4-Pad123)") (class "Default")
      (node (ref "J4") (pin "123") (pinfunction "123_123") (pintype "passive"))
    )
    (net (code "153") (name "unconnected-(J4-Pad125)") (class "Default")
      (node (ref "J4") (pin "125") (pinfunction "125_125") (pintype "passive"))
    )
    (net (code "154") (name "unconnected-(J4-Pad126)") (class "Default")
      (node (ref "J4") (pin "126") (pinfunction "126_126") (pintype "passive"))
    )
    (net (code "155") (name "unconnected-(J4-Pad128)") (class "Default")
      (node (ref "J4") (pin "128") (pinfunction "128_128") (pintype "passive"))
    )
    (net (code "156") (name "unconnected-(J4-Pad129)") (class "Default")
      (node (ref "J4") (pin "129") (pinfunction "129_129") (pintype "passive"))
    )
    (net (code "157") (name "unconnected-(J4-Pad132)") (class "Default")
      (node (ref "J4") (pin "132") (pinfunction "132_132") (pintype "passive"))
    )
    (net (code "158") (name "unconnected-(J4-Pad133)") (class "Default")
      (node (ref "J4") (pin "133") (pinfunction "133_133") (pintype "passive"))
    )
    (net (code "159") (name "unconnected-(J4-Pad135)") (class "Default")
      (node (ref "J4") (pin "135") (pinfunction "135_135") (pintype "passive"))
    )
    (net (code "160") (name "unconnected-(J4-Pad136)") (class "Default")
      (node (ref "J4") (pin "136") (pinfunction "136_136") (pintype "passive"))
    )
    (net (code "161") (name "unconnected-(J4-Pad138)") (class "Default")
      (node (ref "J4") (pin "138") (pinfunction "138_138") (pintype "passive"))
    )
    (net (code "162") (name "unconnected-(J4-Pad139)") (class "Default")
      (node (ref "J4") (pin "139") (pinfunction "139_139") (pintype "passive"))
    )
    (net (code "163") (name "unconnected-(J4-Pad142)") (class "Default")
      (node (ref "J4") (pin "142") (pinfunction "142_142") (pintype "passive"))
    )
    (net (code "164") (name "unconnected-(J4-Pad143)") (class "Default")
      (node (ref "J4") (pin "143") (pinfunction "143_143") (pintype "passive"))
    )
    (net (code "165") (name "unconnected-(J4-Pad145)") (class "Default")
      (node (ref "J4") (pin "145") (pinfunction "145_145") (pintype "passive"))
    )
    (net (code "166") (name "unconnected-(J4-Pad146)") (class "Default")
      (node (ref "J4") (pin "146") (pinfunction "146_146") (pintype "passive"))
    )
    (net (code "167") (name "unconnected-(J4-Pad148)") (class "Default")
      (node (ref "J4") (pin "148") (pinfunction "148_148") (pintype "passive"))
    )
    (net (code "168") (name "unconnected-(J4-Pad149)") (class "Default")
      (node (ref "J4") (pin "149") (pinfunction "149_149") (pintype "passive"))
    )
    (net (code "169") (name "unconnected-(J4-Pad152)") (class "Default")
      (node (ref "J4") (pin "152") (pinfunction "152_152") (pintype "passive"))
    )
    (net (code "170") (name "unconnected-(J4-Pad153)") (class "Default")
      (node (ref "J4") (pin "153") (pinfunction "153_153") (pintype "passive"))
    )
    (net (code "171") (name "unconnected-(J4-Pad155)") (class "Default")
      (node (ref "J4") (pin "155") (pinfunction "155_155") (pintype "passive"))
    )
    (net (code "172") (name "unconnected-(J4-Pad156)") (class "Default")
      (node (ref "J4") (pin "156") (pinfunction "156_156") (pintype "passive"))
    )
    (net (code "173") (name "unconnected-(J4-Pad158)") (class "Default")
      (node (ref "J4") (pin "158") (pinfunction "158_158") (pintype "passive"))
    )
    (net (code "174") (name "unconnected-(J4-Pad159)") (class "Default")
      (node (ref "J4") (pin "159") (pinfunction "159_159") (pintype "passive"))
    )
    (net (code "175") (name "unconnected-(J4-Pad319)") (class "Default")
      (node (ref "J4") (pin "319") (pinfunction "319_319") (pintype "passive+no_connect"))
    )
    (net (code "176") (name "unconnected-(J4-Pad322)") (class "Default")
      (node (ref "J4") (pin "322") (pinfunction "322_322") (pintype "passive"))
    )
    (net (code "177") (name "unconnected-(J4-Pad323)") (class "Default")
      (node (ref "J4") (pin "323") (pinfunction "323_323") (pintype "passive"))
    )
    (net (code "178") (name "unconnected-(J4-Pad325)") (class "Default")
      (node (ref "J4") (pin "325") (pinfunction "325_325") (pintype "passive"))
    )
    (net (code "179") (name "unconnected-(J4-Pad326)") (class "Default")
      (node (ref "J4") (pin "326") (pinfunction "326_326") (pintype "passive"))
    )
    (net (code "180") (name "unconnected-(J4-Pad328)") (class "Default")
      (node (ref "J4") (pin "328") (pinfunction "328_328") (pintype "passive"))
    )
    (net (code "181") (name "unconnected-(J4-Pad329)") (class "Default")
      (node (ref "J4") (pin "329") (pinfunction "329_329") (pintype "passive"))
    )
    (net (code "182") (name "unconnected-(J4-Pad332)") (class "Default")
      (node (ref "J4") (pin "332") (pinfunction "332_332") (pintype "passive"))
    )
    (net (code "183") (name "unconnected-(J4-Pad333)") (class "Default")
      (node (ref "J4") (pin "333") (pinfunction "333_333") (pintype "passive"))
    )
    (net (code "184") (name "unconnected-(J4-Pad335)") (class "Default")
      (node (ref "J4") (pin "335") (pinfunction "335_335") (pintype "passive"))
    )
    (net (code "185") (name "unconnected-(J4-Pad336)") (class "Default")
      (node (ref "J4") (pin "336") (pinfunction "336_336") (pintype "passive"))
    )
    (net (code "186") (name "unconnected-(J4-Pad338)") (class "Default")
      (node (ref "J4") (pin "338") (pinfunction "338_338") (pintype "passive"))
    )
    (net (code "187") (name "unconnected-(J4-Pad339)") (class "Default")
      (node (ref "J4") (pin "339") (pinfunction "339_339") (pintype "passive"))
    )
    (net (code "188") (name "unconnected-(J4-Pad342)") (class "Default")
      (node (ref "J4") (pin "342") (pinfunction "342_342") (pintype "passive"))
    )
    (net (code "189") (name "unconnected-(J4-Pad343)") (class "Default")
      (node (ref "J4") (pin "343") (pinfunction "343_343") (pintype "passive"))
    )
    (net (code "190") (name "unconnected-(J4-Pad345)") (class "Default")
      (node (ref "J4") (pin "345") (pinfunction "345_345") (pintype "passive"))
    )
    (net (code "191") (name "unconnected-(J4-Pad346)") (class "Default")
      (node (ref "J4") (pin "346") (pinfunction "346_346") (pintype "passive"))
    )
    (net (code "192") (name "unconnected-(J4-Pad348)") (class "Default")
      (node (ref "J4") (pin "348") (pinfunction "348_348") (pintype "passive"))
    )
    (net (code "193") (name "unconnected-(J4-Pad349)") (class "Default")
      (node (ref "J4") (pin "349") (pinfunction "349_349") (pintype "passive"))
    )
    (net (code "194") (name "unconnected-(J4-Pad352)") (class "Default")
      (node (ref "J4") (pin "352") (pinfunction "352_352") (pintype "passive"))
    )
    (net (code "195") (name "unconnected-(J4-Pad353)") (class "Default")
      (node (ref "J4") (pin "353") (pinfunction "353_353") (pintype "passive"))
    )
    (net (code "196") (name "unconnected-(J4-Pad355)") (class "Default")
      (node (ref "J4") (pin "355") (pinfunction "355_355") (pintype "passive"))
    )
    (net (code "197") (name "unconnected-(J4-Pad356)") (class "Default")
      (node (ref "J4") (pin "356") (pinfunction "356_356") (pintype "passive"))
    )
    (net (code "198") (name "unconnected-(J4-Pad358)") (class "Default")
      (node (ref "J4") (pin "358") (pinfunction "358_358") (pintype "passive"))
    )
    (net (code "199") (name "unconnected-(J4-Pad359)") (class "Default")
      (node (ref "J4") (pin "359") (pinfunction "359_359") (pintype "passive"))
    )
    (net (code "200") (name "unconnected-(J4-Pad362)") (class "Default")
      (node (ref "J4") (pin "362") (pinfunction "362_362") (pintype "passive"))
    )
    (net (code "201") (name "unconnected-(J4-Pad363)") (class "Default")
      (node (ref "J4") (pin "363") (pinfunction "363_363") (pintype "passive"))
    )
    (net (code "202") (name "unconnected-(J4-Pad365)") (class "Default")
      (node (ref "J4") (pin "365") (pinfunction "365_365") (pintype "passive"))
    )
    (net (code "203") (name "unconnected-(J4-Pad366)") (class "Default")
      (node (ref "J4") (pin "366") (pinfunction "366_366") (pintype "passive"))
    )
    (net (code "204") (name "unconnected-(J4-Pad368)") (class "Default")
      (node (ref "J4") (pin "368") (pinfunction "368_368") (pintype "passive"))
    )
    (net (code "205") (name "unconnected-(J4-Pad369)") (class "Default")
      (node (ref "J4") (pin "369") (pinfunction "369_369") (pintype "passive"))
    )
    (net (code "206") (name "unconnected-(J4-Pad372)") (class "Default")
      (node (ref "J4") (pin "372") (pinfunction "372_372") (pintype "passive"))
    )
    (net (code "207") (name "unconnected-(J4-Pad373)") (class "Default")
      (node (ref "J4") (pin "373") (pinfunction "373_373") (pintype "passive"))
    )
    (net (code "208") (name "unconnected-(J4-Pad375)") (class "Default")
      (node (ref "J4") (pin "375") (pinfunction "375_375") (pintype "passive"))
    )
    (net (code "209") (name "unconnected-(J4-Pad376)") (class "Default")
      (node (ref "J4") (pin "376") (pinfunction "376_376") (pintype "passive"))
    )
    (net (code "210") (name "unconnected-(J4-Pad378)") (class "Default")
      (node (ref "J4") (pin "378") (pinfunction "378_378") (pintype "passive"))
    )
    (net (code "211") (name "unconnected-(J4-Pad379)") (class "Default")
      (node (ref "J4") (pin "379") (pinfunction "379_379") (pintype "passive"))
    )
    (net (code "212") (name "unconnected-(J4-Pad382)") (class "Default")
      (node (ref "J4") (pin "382") (pinfunction "382_382") (pintype "passive"))
    )
    (net (code "213") (name "unconnected-(J4-Pad383)") (class "Default")
      (node (ref "J4") (pin "383") (pinfunction "383_383") (pintype "passive"))
    )
    (net (code "214") (name "unconnected-(J4-Pad385)") (class "Default")
      (node (ref "J4") (pin "385") (pinfunction "385_385") (pintype "passive"))
    )
    (net (code "215") (name "unconnected-(J4-Pad386)") (class "Default")
      (node (ref "J4") (pin "386") (pinfunction "386_386") (pintype "passive"))
    )
    (net (code "216") (name "unconnected-(J4-Pad388)") (class "Default")
      (node (ref "J4") (pin "388") (pinfunction "388_388") (pintype "passive"))
    )
    (net (code "217") (name "unconnected-(J4-Pad389)") (class "Default")
      (node (ref "J4") (pin "389") (pinfunction "389_389") (pintype "passive"))
    )
    (net (code "218") (name "unconnected-(J4-Pad392)") (class "Default")
      (node (ref "J4") (pin "392") (pinfunction "392_392") (pintype "passive"))
    )
    (net (code "219") (name "unconnected-(J4-Pad393)") (class "Default")
      (node (ref "J4") (pin "393") (pinfunction "393_393") (pintype "passive"))
    )
    (net (code "220") (name "unconnected-(J4-Pad395)") (class "Default")
      (node (ref "J4") (pin "395") (pinfunction "395_395") (pintype "passive"))
    )
    (net (code "221") (name "unconnected-(J4-Pad396)") (class "Default")
      (node (ref "J4") (pin "396") (pinfunction "396_396") (pintype "passive"))
    )
    (net (code "222") (name "unconnected-(J4-Pad398)") (class "Default")
      (node (ref "J4") (pin "398") (pinfunction "398_398") (pintype "passive"))
    )
    (net (code "223") (name "unconnected-(J4-Pad399)") (class "Default")
      (node (ref "J4") (pin "399") (pinfunction "399_399") (pintype "passive"))
    )
  )
)
